# WiFiSensorLTC3566.net
KiCad netlist of a schematic drawn in EAGLE
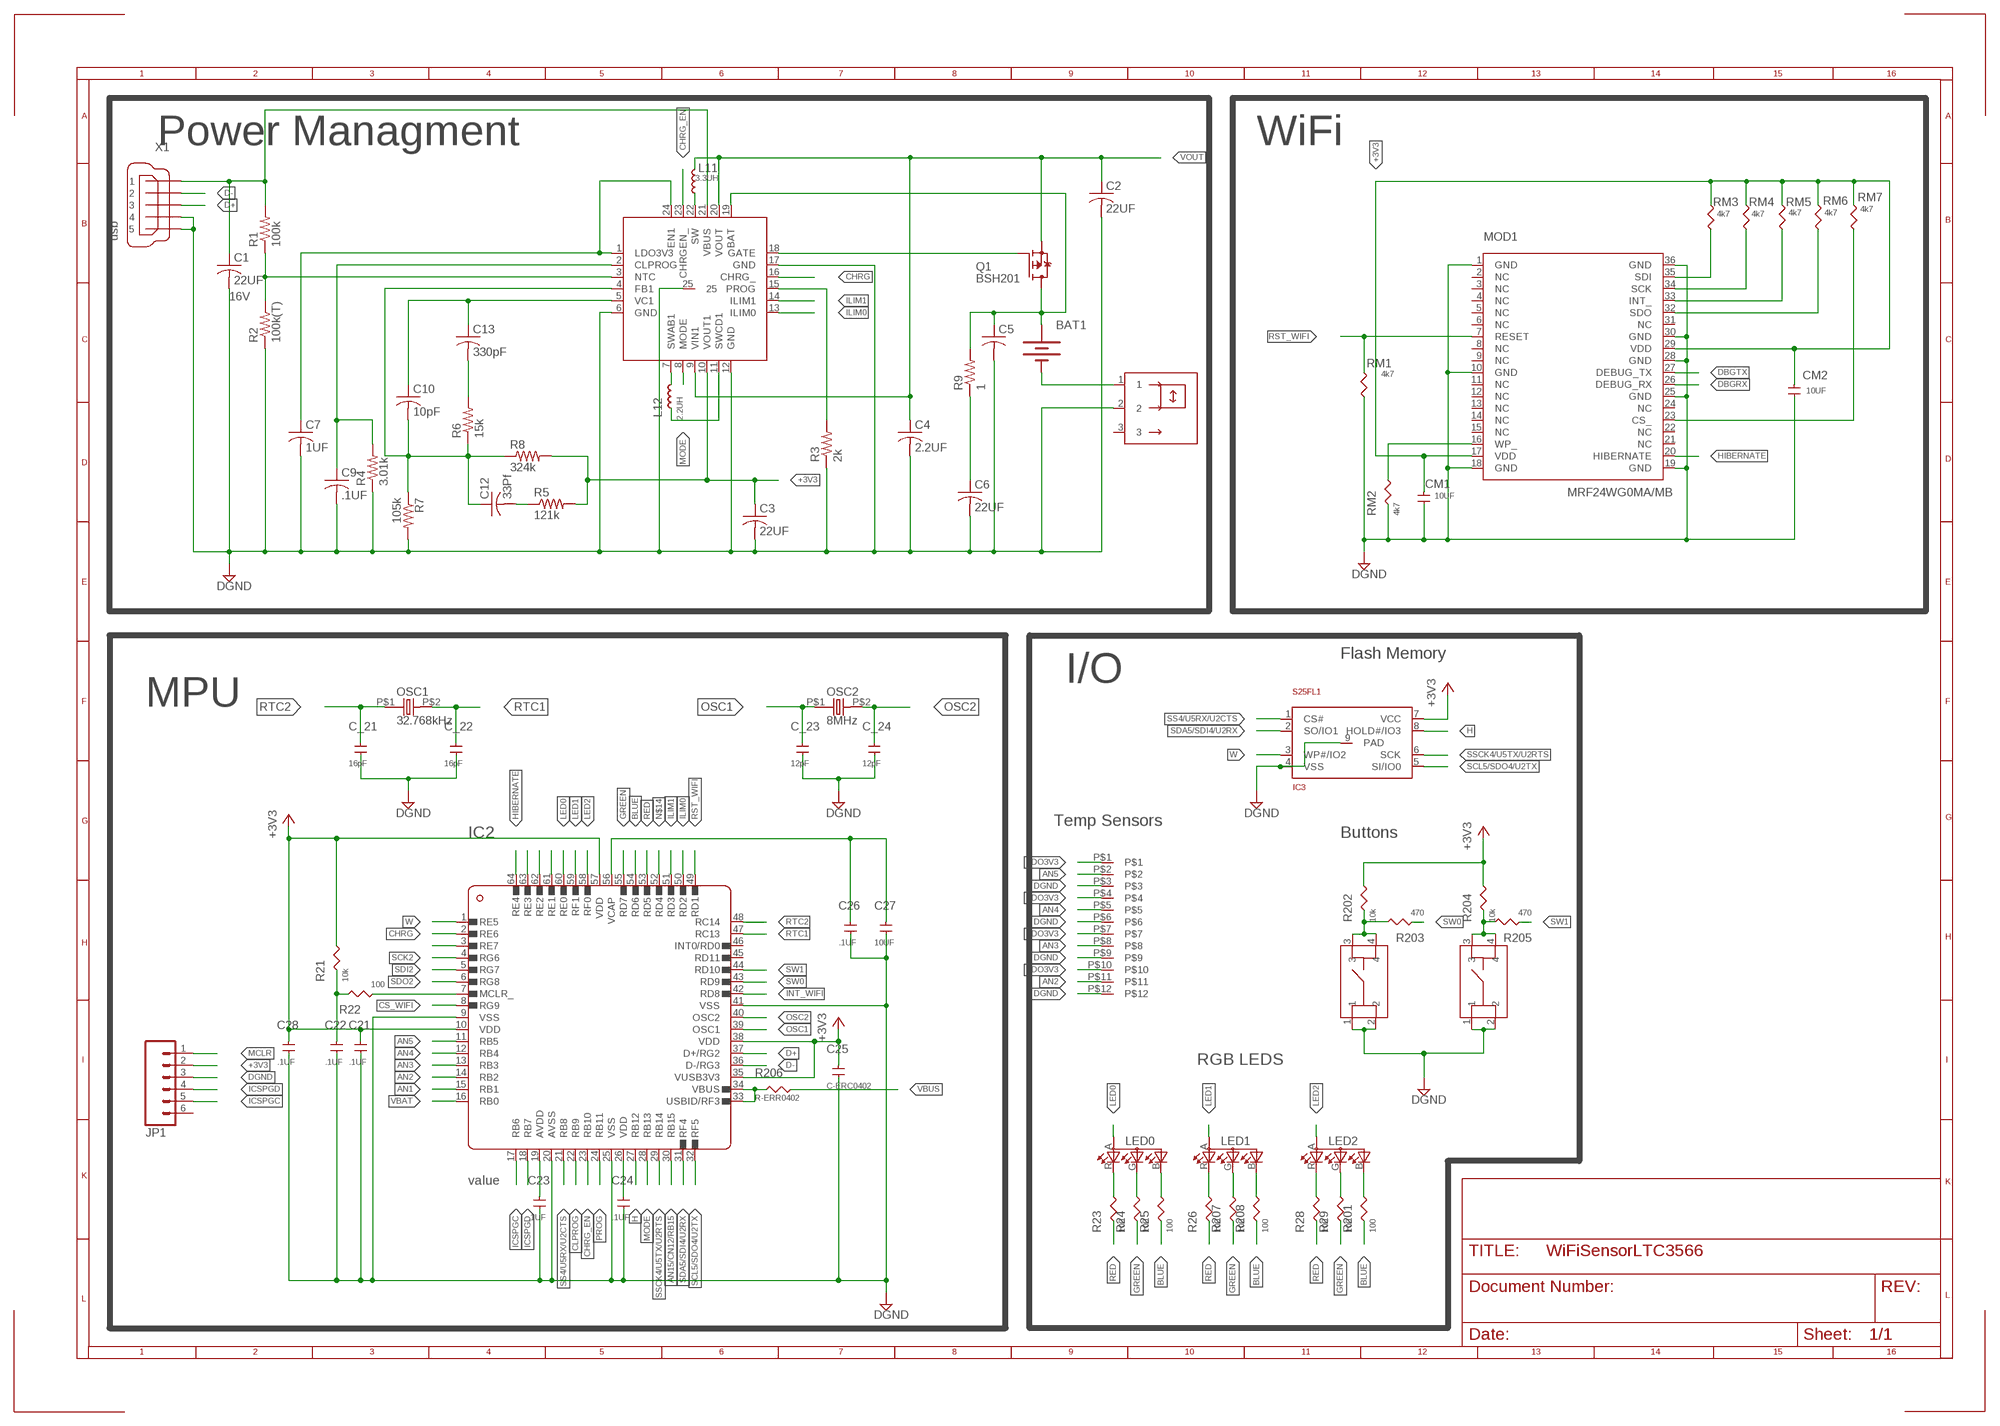
[diagram p0: schematic, sheet 1]

(export (version "E")
  (design (tool "Eeschema 10.0.6"))
  (components
    (comp (ref "BAT1")
      (value "BATTERY245PTH")
      (footprint "eagle-import:BATTCON_245MM_PTH")
      (libsource (lib "eagle-import") (part "BATTERY245PTH"))
    )
    (comp (ref "C1")
      (value "22UF")
      (footprint "eagle-import:C0805")
      (fields (field (name "VOLTAGECOEFFECIENT") "16V"))
      (libsource (lib "eagle-import") (part "C-USC0805"))
    )
    (comp (ref "C2")
      (value "22UF")
      (footprint "eagle-import:C0805")
      (libsource (lib "eagle-import") (part "C-USC0805"))
    )
    (comp (ref "C3")
      (value "22UF")
      (footprint "eagle-import:C0805")
      (libsource (lib "eagle-import") (part "C-USC0805"))
    )
    (comp (ref "C4")
      (value "2.2UF")
      (footprint "eagle-import:C0805")
      (libsource (lib "eagle-import") (part "C-USC0805"))
    )
    (comp (ref "C5")
      (value "C-USC0402")
      (footprint "eagle-import:C0402")
      (libsource (lib "eagle-import") (part "C-USC0402"))
    )
    (comp (ref "C6")
      (value "22UF")
      (footprint "eagle-import:C0805")
      (libsource (lib "eagle-import") (part "C-USC0805"))
    )
    (comp (ref "C7")
      (value "1UF")
      (footprint "eagle-import:C0805")
      (libsource (lib "eagle-import") (part "C-USC0805"))
    )
    (comp (ref "C9")
      (value ".1UF")
      (footprint "eagle-import:C0402")
      (libsource (lib "eagle-import") (part "C-USC0402"))
    )
    (comp (ref "C10")
      (value "10pF")
      (footprint "eagle-import:C0402")
      (libsource (lib "eagle-import") (part "C-USC0402"))
    )
    (comp (ref "C12")
      (value "33Pf")
      (footprint "eagle-import:C0402")
      (libsource (lib "eagle-import") (part "C-USC0402"))
    )
    (comp (ref "C13")
      (value "330pF")
      (footprint "eagle-import:C0402")
      (libsource (lib "eagle-import") (part "C-USC0402"))
    )
    (comp (ref "C21")
      (value ".1UF")
      (footprint "eagle-import:C0402")
      (libsource (lib "eagle-import") (part "C-ERC0402"))
    )
    (comp (ref "C22")
      (value ".1UF")
      (footprint "eagle-import:C0402")
      (libsource (lib "eagle-import") (part "C-ERC0402"))
    )
    (comp (ref "C23")
      (value ".1UF")
      (footprint "eagle-import:C0402")
      (libsource (lib "eagle-import") (part "C-ERC0402"))
    )
    (comp (ref "C24")
      (value ".1UF")
      (footprint "eagle-import:C0402")
      (libsource (lib "eagle-import") (part "C-ERC0402"))
    )
    (comp (ref "C25")
      (value "C-ERC0402")
      (footprint "eagle-import:C0402")
      (libsource (lib "eagle-import") (part "C-ERC0402"))
    )
    (comp (ref "C26")
      (value ".1UF")
      (footprint "eagle-import:C0402")
      (libsource (lib "eagle-import") (part "C-ERC0402"))
    )
    (comp (ref "C27")
      (value "10UF")
      (footprint "eagle-import:C0805")
      (libsource (lib "eagle-import") (part "C-ER"))
    )
    (comp (ref "C28")
      (value ".1UF")
      (footprint "eagle-import:C0402")
      (libsource (lib "eagle-import") (part "C-ERC0402"))
    )
    (comp (ref "CM1")
      (value "10UF")
      (footprint "eagle-import:C0805")
      (libsource (lib "eagle-import") (part "C-ER"))
    )
    (comp (ref "CM2")
      (value "10UF")
      (footprint "eagle-import:C0805")
      (libsource (lib "eagle-import") (part "C-ER"))
    )
    (comp (ref "C_21")
      (value "16pF")
      (footprint "eagle-import:C0402")
      (libsource (lib "eagle-import") (part "C-ERC0402"))
    )
    (comp (ref "C_22")
      (value "16pF")
      (footprint "eagle-import:C0402")
      (libsource (lib "eagle-import") (part "C-ERC0402"))
    )
    (comp (ref "C_23")
      (value "12pF")
      (footprint "eagle-import:C0402")
      (libsource (lib "eagle-import") (part "C-ERC0402"))
    )
    (comp (ref "C_24")
      (value "12pF")
      (footprint "eagle-import:C0402")
      (libsource (lib "eagle-import") (part "C-ERC0402"))
    )
    (comp (ref "IC1")
      (value "LTC3566-2")
      (footprint "eagle-import:QFN24-4X4")
      (libsource (lib "eagle-import") (part "LTC3566"))
    )
    (comp (ref "IC2")
      (value "PICMX32695F512H")
      (footprint "eagle-import:TQFP64")
      (libsource (lib "eagle-import") (part "PICMX32695F512H"))
    )
    (comp (ref "IC3")
      (value "S25FL1")
      (footprint "eagle-import:8WSON")
      (libsource (lib "eagle-import") (part "S25FL1"))
    )
    (comp (ref "JP1")
      (value "M06LOCK")
      (footprint "eagle-import:1X06_LOCK")
      (libsource (lib "eagle-import") (part "M06LOCK"))
    )
    (comp (ref "JP2")
      (value "12_127")
      (footprint "eagle-import:12-127")
      (libsource (lib "eagle-import") (part "12_127"))
    )
    (comp (ref "L11")
      (value "3.3UH")
      (footprint "eagle-import:VLCF5020")
      (libsource (lib "eagle-import") (part "L-ERVLCF5020"))
    )
    (comp (ref "L12")
      (value "2.2UH")
      (footprint "eagle-import:VLCF5020")
      (libsource (lib "eagle-import") (part "L-ERVLCF5020"))
    )
    (comp (ref "LED0")
      (value "1X1RGB")
      (footprint "eagle-import:1X1")
      (libsource (lib "eagle-import") (part "1X1RGB"))
    )
    (comp (ref "LED1")
      (value "1X1RGB")
      (footprint "eagle-import:1X1")
      (libsource (lib "eagle-import") (part "1X1RGB"))
    )
    (comp (ref "LED2")
      (value "1X1RGB")
      (footprint "eagle-import:1X1")
      (libsource (lib "eagle-import") (part "1X1RGB"))
    )
    (comp (ref "MOD1")
      (value "MRF24WG0MA/MB")
      (footprint "eagle-import:MRF24")
      (libsource (lib "eagle-import") (part "MRF24WG0MA/MB"))
    )
    (comp (ref "OSC1")
      (value "32.768kHz")
      (footprint "eagle-import:ECX39")
      (fields (field (name "DIGIPART") "XC1658CT-ND"))
      (libsource (lib "eagle-import") (part "ECX32"))
    )
    (comp (ref "OSC2")
      (value "8MHz")
      (footprint "eagle-import:CX532")
      (fields (field (name "DIGIPART") "XC1658CT-ND"))
      (libsource (lib "eagle-import") (part "CX532"))
    )
    (comp (ref "Q1")
      (value "BSH201")
      (footprint "eagle-import:SOT23")
      (libsource (lib "eagle-import") (part "BSH201"))
    )
    (comp (ref "R1")
      (value "100k")
      (footprint "eagle-import:R0402")
      (libsource (lib "eagle-import") (part "R-US_R0402"))
    )
    (comp (ref "R2")
      (value "100k(T)")
      (footprint "eagle-import:R0402")
      (libsource (lib "eagle-import") (part "R-US_R0402"))
    )
    (comp (ref "R3")
      (value "2k")
      (footprint "eagle-import:R0402")
      (libsource (lib "eagle-import") (part "R-US_R0402"))
    )
    (comp (ref "R4")
      (value "3.01k")
      (footprint "eagle-import:R0402")
      (libsource (lib "eagle-import") (part "R-US_R0402"))
    )
    (comp (ref "R5")
      (value "121k")
      (footprint "eagle-import:R0402")
      (libsource (lib "eagle-import") (part "R-US_R0402"))
    )
    (comp (ref "R6")
      (value "15k")
      (footprint "eagle-import:R0402")
      (libsource (lib "eagle-import") (part "R-US_R0402"))
    )
    (comp (ref "R7")
      (value "105k")
      (footprint "eagle-import:R0402")
      (libsource (lib "eagle-import") (part "R-US_R0402"))
    )
    (comp (ref "R8")
      (value "324k")
      (footprint "eagle-import:R0402")
      (libsource (lib "eagle-import") (part "R-US_R0402"))
    )
    (comp (ref "R9")
      (value "1")
      (footprint "eagle-import:R0402")
      (libsource (lib "eagle-import") (part "R-US_R0402"))
    )
    (comp (ref "R21")
      (value "10k")
      (footprint "eagle-import:R0402")
      (libsource (lib "eagle-import") (part "R-ERR0402"))
    )
    (comp (ref "R22")
      (value "100")
      (footprint "eagle-import:R0402")
      (libsource (lib "eagle-import") (part "R-ERR0402"))
    )
    (comp (ref "R23")
      (value "100")
      (footprint "eagle-import:R0402")
      (libsource (lib "eagle-import") (part "R-ERR0402"))
    )
    (comp (ref "R24")
      (value "100")
      (footprint "eagle-import:R0402")
      (libsource (lib "eagle-import") (part "R-ERR0402"))
    )
    (comp (ref "R25")
      (value "100")
      (footprint "eagle-import:R0402")
      (libsource (lib "eagle-import") (part "R-ERR0402"))
    )
    (comp (ref "R26")
      (value "100")
      (footprint "eagle-import:R0402")
      (libsource (lib "eagle-import") (part "R-ERR0402"))
    )
    (comp (ref "R28")
      (value "100")
      (footprint "eagle-import:R0402")
      (libsource (lib "eagle-import") (part "R-ERR0402"))
    )
    (comp (ref "R29")
      (value "100")
      (footprint "eagle-import:R0402")
      (libsource (lib "eagle-import") (part "R-ERR0402"))
    )
    (comp (ref "R201")
      (value "100")
      (footprint "eagle-import:R0402")
      (libsource (lib "eagle-import") (part "R-ERR0402"))
    )
    (comp (ref "R202")
      (value "10k")
      (footprint "eagle-import:R0402")
      (libsource (lib "eagle-import") (part "R-ERR0402"))
    )
    (comp (ref "R203")
      (value "470")
      (footprint "eagle-import:R0402")
      (libsource (lib "eagle-import") (part "R-ERR0402"))
    )
    (comp (ref "R204")
      (value "10k")
      (footprint "eagle-import:R0402")
      (libsource (lib "eagle-import") (part "R-ERR0402"))
    )
    (comp (ref "R205")
      (value "470")
      (footprint "eagle-import:R0402")
      (libsource (lib "eagle-import") (part "R-ERR0402"))
    )
    (comp (ref "R206")
      (value "R-ERR0402")
      (footprint "eagle-import:R0402")
      (libsource (lib "eagle-import") (part "R-ERR0402"))
    )
    (comp (ref "R207")
      (value "100")
      (footprint "eagle-import:R0402")
      (libsource (lib "eagle-import") (part "R-ERR0402"))
    )
    (comp (ref "R208")
      (value "100")
      (footprint "eagle-import:R0402")
      (libsource (lib "eagle-import") (part "R-ERR0402"))
    )
    (comp (ref "RM1")
      (value "4k7")
      (footprint "eagle-import:R0402")
      (libsource (lib "eagle-import") (part "R-ERR0402"))
    )
    (comp (ref "RM2")
      (value "4k7")
      (footprint "eagle-import:R0402")
      (libsource (lib "eagle-import") (part "R-ERR0402"))
    )
    (comp (ref "RM3")
      (value "4k7")
      (footprint "eagle-import:R0402")
      (libsource (lib "eagle-import") (part "R-ERR0402"))
    )
    (comp (ref "RM4")
      (value "4k7")
      (footprint "eagle-import:R0402")
      (libsource (lib "eagle-import") (part "R-ERR0402"))
    )
    (comp (ref "RM5")
      (value "4k7")
      (footprint "eagle-import:R0402")
      (libsource (lib "eagle-import") (part "R-ERR0402"))
    )
    (comp (ref "RM6")
      (value "4k7")
      (footprint "eagle-import:R0402")
      (libsource (lib "eagle-import") (part "R-ERR0402"))
    )
    (comp (ref "RM7")
      (value "4k7")
      (footprint "eagle-import:R0402")
      (libsource (lib "eagle-import") (part "R-ERR0402"))
    )
    (comp (ref "SW0")
      (value "ADTS")
      (footprint "eagle-import:4X5")
      (libsource (lib "eagle-import") (part "ADTS"))
    )
    (comp (ref "SW1")
      (value "ADTS")
      (footprint "eagle-import:4X5")
      (libsource (lib "eagle-import") (part "ADTS"))
    )
    (comp (ref "SW2")
      (value "C&K_JS")
      (footprint "eagle-import:SAQN")
      (libsource (lib "eagle-import") (part "C&K_JS"))
    )
    (comp (ref "X1")
      (value "usb")
      (footprint "eagle-import:UX60A-MB-5ST")
      (libsource (lib "eagle-import") (part "MINI-USB-UX60A-MB-5ST"))
    )
  )
  (nets
    (net (code "1") (name "+3V3") (class "Default")
      (node (ref "C21") (pin "2") (pinfunction "P$2_2") (pintype "bidirectional"))
      (node (ref "C24") (pin "2") (pinfunction "P$2_2") (pintype "bidirectional"))
      (node (ref "C25") (pin "2") (pinfunction "P$2_2") (pintype "bidirectional"))
      (node (ref "C28") (pin "2") (pinfunction "P$2_2") (pintype "bidirectional"))
      (node (ref "C3") (pin "1") (pinfunction "1_1") (pintype "passive"))
      (node (ref "CM1") (pin "2") (pinfunction "P$2_2") (pintype "bidirectional"))
      (node (ref "CM2") (pin "2") (pinfunction "P$2_2") (pintype "bidirectional"))
      (node (ref "IC1") (pin "10") (pinfunction "VOUT1_10") (pintype "bidirectional"))
      (node (ref "IC2") (pin "10") (pinfunction "VDD_10") (pintype "bidirectional"))
      (node (ref "IC2") (pin "26") (pinfunction "VDD_26") (pintype "bidirectional"))
      (node (ref "IC2") (pin "35") (pinfunction "VUSB3V3_35") (pintype "bidirectional"))
      (node (ref "IC2") (pin "38") (pinfunction "VDD_38") (pintype "bidirectional"))
      (node (ref "IC2") (pin "57") (pinfunction "VDD_57") (pintype "bidirectional"))
      (node (ref "IC3") (pin "7") (pinfunction "VCC_7") (pintype "bidirectional"))
      (node (ref "JP1") (pin "2") (pinfunction "2_2") (pintype "passive"))
      (node (ref "MOD1") (pin "17") (pinfunction "VDD_17") (pintype "bidirectional"))
      (node (ref "MOD1") (pin "29") (pinfunction "VDD_29") (pintype "bidirectional"))
      (node (ref "R202") (pin "2") (pinfunction "P$2_2") (pintype "bidirectional"))
      (node (ref "R204") (pin "2") (pinfunction "P$2_2") (pintype "bidirectional"))
      (node (ref "R21") (pin "2") (pinfunction "P$2_2") (pintype "bidirectional"))
      (node (ref "R5") (pin "2") (pinfunction "2_2") (pintype "passive"))
      (node (ref "R8") (pin "2") (pinfunction "2_2") (pintype "passive"))
      (node (ref "RM3") (pin "2") (pinfunction "P$2_2") (pintype "bidirectional"))
      (node (ref "RM4") (pin "2") (pinfunction "P$2_2") (pintype "bidirectional"))
      (node (ref "RM5") (pin "2") (pinfunction "P$2_2") (pintype "bidirectional"))
      (node (ref "RM6") (pin "2") (pinfunction "P$2_2") (pintype "bidirectional"))
      (node (ref "RM7") (pin "2") (pinfunction "P$2_2") (pintype "bidirectional"))
    )
    (net (code "2") (name "AN1") (class "Default")
      (node (ref "IC2") (pin "15") (pinfunction "RB1_15") (pintype "bidirectional"))
    )
    (net (code "3") (name "AN2") (class "Default")
      (node (ref "IC2") (pin "14") (pinfunction "RB2_14") (pintype "bidirectional"))
      (node (ref "JP2") (pin "P$11") (pinfunction "P$11_P$11") (pintype "bidirectional"))
    )
    (net (code "4") (name "AN3") (class "Default")
      (node (ref "IC2") (pin "13") (pinfunction "RB3_13") (pintype "bidirectional"))
      (node (ref "JP2") (pin "P$8") (pinfunction "P$8_P$8") (pintype "bidirectional"))
    )
    (net (code "5") (name "AN4") (class "Default")
      (node (ref "IC2") (pin "12") (pinfunction "RB4_12") (pintype "bidirectional"))
      (node (ref "JP2") (pin "P$5") (pinfunction "P$5_P$5") (pintype "bidirectional"))
    )
    (net (code "6") (name "AN5") (class "Default")
      (node (ref "IC2") (pin "11") (pinfunction "RB5_11") (pintype "bidirectional"))
      (node (ref "JP2") (pin "P$2") (pinfunction "P$2_P$2") (pintype "bidirectional"))
    )
    (net (code "7") (name "AN15{slash}CN12{slash}RB15") (class "Default")
      (node (ref "IC2") (pin "30") (pinfunction "RB15_30") (pintype "bidirectional"))
    )
    (net (code "8") (name "BLUE") (class "Default")
      (node (ref "IC2") (pin "54") (pinfunction "RD6_54") (pintype "bidirectional"))
      (node (ref "R201") (pin "1") (pinfunction "P$1_1") (pintype "bidirectional"))
      (node (ref "R208") (pin "1") (pinfunction "P$1_1") (pintype "bidirectional"))
      (node (ref "R25") (pin "1") (pinfunction "P$1_1") (pintype "bidirectional"))
    )
    (net (code "9") (name "CHRG") (class "Default")
      (node (ref "IC1") (pin "16") (pinfunction "CHRG__16") (pintype "bidirectional"))
      (node (ref "IC2") (pin "2") (pinfunction "RE6_2") (pintype "bidirectional"))
    )
    (net (code "10") (name "CHRG_EN") (class "Default")
      (node (ref "IC1") (pin "23") (pinfunction "CHRGEN__23") (pintype "bidirectional"))
      (node (ref "IC2") (pin "23") (pinfunction "RB10_23") (pintype "bidirectional"))
    )
    (net (code "11") (name "CLPROG") (class "Default")
      (node (ref "C9") (pin "1") (pinfunction "1_1") (pintype "passive"))
      (node (ref "IC1") (pin "2") (pinfunction "CLPROG_2") (pintype "bidirectional"))
      (node (ref "IC2") (pin "22") (pinfunction "RB9_22") (pintype "bidirectional"))
      (node (ref "R4") (pin "2") (pinfunction "2_2") (pintype "passive"))
    )
    (net (code "12") (name "CS_WIFI") (class "Default")
      (node (ref "IC2") (pin "8") (pinfunction "RG9_8") (pintype "bidirectional"))
      (node (ref "MOD1") (pin "23") (pinfunction "CS__23") (pintype "bidirectional"))
      (node (ref "RM7") (pin "1") (pinfunction "P$1_1") (pintype "bidirectional"))
    )
    (net (code "13") (name "D+") (class "Default")
      (node (ref "IC2") (pin "37") (pinfunction "D+/RG2_37") (pintype "bidirectional"))
      (node (ref "X1") (pin "3") (pinfunction "3_3") (pintype "input"))
    )
    (net (code "14") (name "D-") (class "Default")
      (node (ref "IC2") (pin "36") (pinfunction "D-/RG3_36") (pintype "bidirectional"))
      (node (ref "X1") (pin "2") (pinfunction "2_2") (pintype "input"))
    )
    (net (code "15") (name "DBGRX") (class "Default")
      (node (ref "MOD1") (pin "26") (pinfunction "DEBUG_RX_26") (pintype "bidirectional"))
    )
    (net (code "16") (name "DBGTX") (class "Default")
      (node (ref "MOD1") (pin "27") (pinfunction "DEBUG_TX_27") (pintype "bidirectional"))
    )
    (net (code "17") (name "DGND") (class "Default")
      (node (ref "C1") (pin "2") (pinfunction "2_2") (pintype "passive"))
      (node (ref "C2") (pin "2") (pinfunction "2_2") (pintype "passive"))
      (node (ref "C21") (pin "1") (pinfunction "P$1_1") (pintype "bidirectional"))
      (node (ref "C22") (pin "1") (pinfunction "P$1_1") (pintype "bidirectional"))
      (node (ref "C23") (pin "1") (pinfunction "P$1_1") (pintype "bidirectional"))
      (node (ref "C24") (pin "1") (pinfunction "P$1_1") (pintype "bidirectional"))
      (node (ref "C25") (pin "1") (pinfunction "P$1_1") (pintype "bidirectional"))
      (node (ref "C26") (pin "1") (pinfunction "P$1_1") (pintype "bidirectional"))
      (node (ref "C27") (pin "1") (pinfunction "P$1_1") (pintype "bidirectional"))
      (node (ref "C28") (pin "1") (pinfunction "P$1_1") (pintype "bidirectional"))
      (node (ref "C3") (pin "2") (pinfunction "2_2") (pintype "passive"))
      (node (ref "C4") (pin "2") (pinfunction "2_2") (pintype "passive"))
      (node (ref "C5") (pin "2") (pinfunction "2_2") (pintype "passive"))
      (node (ref "C6") (pin "2") (pinfunction "2_2") (pintype "passive"))
      (node (ref "C7") (pin "2") (pinfunction "2_2") (pintype "passive"))
      (node (ref "C9") (pin "2") (pinfunction "2_2") (pintype "passive"))
      (node (ref "CM1") (pin "1") (pinfunction "P$1_1") (pintype "bidirectional"))
      (node (ref "CM2") (pin "1") (pinfunction "P$1_1") (pintype "bidirectional"))
      (node (ref "C_21") (pin "1") (pinfunction "P$1_1") (pintype "bidirectional"))
      (node (ref "C_22") (pin "1") (pinfunction "P$1_1") (pintype "bidirectional"))
      (node (ref "C_23") (pin "1") (pinfunction "P$1_1") (pintype "bidirectional"))
      (node (ref "C_24") (pin "1") (pinfunction "P$1_1") (pintype "bidirectional"))
      (node (ref "IC1") (pin "12") (pinfunction "GND_12") (pintype "bidirectional"))
      (node (ref "IC1") (pin "17") (pinfunction "GND_17") (pintype "bidirectional"))
      (node (ref "IC1") (pin "25") (pinfunction "25_25") (pintype "bidirectional"))
      (node (ref "IC1") (pin "6") (pinfunction "GND_6") (pintype "bidirectional"))
      (node (ref "IC2") (pin "20") (pinfunction "AVSS_20") (pintype "bidirectional"))
      (node (ref "IC2") (pin "25") (pinfunction "VSS_25") (pintype "bidirectional"))
      (node (ref "IC2") (pin "41") (pinfunction "VSS_41") (pintype "bidirectional"))
      (node (ref "IC2") (pin "9") (pinfunction "VSS_9") (pintype "bidirectional"))
      (node (ref "IC3") (pin "4") (pinfunction "VSS_4") (pintype "bidirectional"))
      (node (ref "IC3") (pin "9") (pinfunction "PAD_9") (pintype "bidirectional"))
      (node (ref "JP1") (pin "3") (pinfunction "3_3") (pintype "passive"))
      (node (ref "JP2") (pin "P$12") (pinfunction "P$12_P$12") (pintype "bidirectional"))
      (node (ref "JP2") (pin "P$3") (pinfunction "P$3_P$3") (pintype "bidirectional"))
      (node (ref "JP2") (pin "P$6") (pinfunction "P$6_P$6") (pintype "bidirectional"))
      (node (ref "JP2") (pin "P$9") (pinfunction "P$9_P$9") (pintype "bidirectional"))
      (node (ref "MOD1") (pin "1") (pinfunction "GND_1") (pintype "bidirectional"))
      (node (ref "MOD1") (pin "10") (pinfunction "GND_10") (pintype "bidirectional"))
      (node (ref "MOD1") (pin "18") (pinfunction "GND_18") (pintype "bidirectional"))
      (node (ref "MOD1") (pin "19") (pinfunction "GND_19") (pintype "bidirectional"))
      (node (ref "MOD1") (pin "25") (pinfunction "GND_25") (pintype "bidirectional"))
      (node (ref "MOD1") (pin "28") (pinfunction "GND_28") (pintype "bidirectional"))
      (node (ref "MOD1") (pin "30") (pinfunction "GND_30") (pintype "bidirectional"))
      (node (ref "MOD1") (pin "36") (pinfunction "GND_36") (pintype "bidirectional"))
      (node (ref "R2") (pin "1") (pinfunction "1_1") (pintype "passive"))
      (node (ref "R3") (pin "1") (pinfunction "1_1") (pintype "passive"))
      (node (ref "R4") (pin "1") (pinfunction "1_1") (pintype "passive"))
      (node (ref "R7") (pin "2") (pinfunction "2_2") (pintype "passive"))
      (node (ref "RM1") (pin "1") (pinfunction "P$1_1") (pintype "bidirectional"))
      (node (ref "RM2") (pin "1") (pinfunction "P$1_1") (pintype "bidirectional"))
      (node (ref "SW0") (pin "1") (pinfunction "1_1") (pintype "bidirectional"))
      (node (ref "SW0") (pin "2") (pinfunction "2_2") (pintype "bidirectional"))
      (node (ref "SW1") (pin "1") (pinfunction "1_1") (pintype "bidirectional"))
      (node (ref "SW1") (pin "2") (pinfunction "2_2") (pintype "bidirectional"))
      (node (ref "SW2") (pin "2") (pinfunction "2_2") (pintype "bidirectional"))
      (node (ref "X1") (pin "4") (pinfunction "4_4") (pintype "input"))
      (node (ref "X1") (pin "5") (pinfunction "5_5") (pintype "input"))
    )
    (net (code "18") (name "GREEN") (class "Default")
      (node (ref "IC2") (pin "55") (pinfunction "RD7_55") (pintype "bidirectional"))
      (node (ref "R207") (pin "1") (pinfunction "P$1_1") (pintype "bidirectional"))
      (node (ref "R24") (pin "1") (pinfunction "P$1_1") (pintype "bidirectional"))
      (node (ref "R29") (pin "1") (pinfunction "P$1_1") (pintype "bidirectional"))
    )
    (net (code "19") (name "H") (class "Default")
      (node (ref "IC2") (pin "27") (pinfunction "RB12_27") (pintype "bidirectional"))
      (node (ref "IC3") (pin "8") (pinfunction "HOLD#/IO3_8") (pintype "bidirectional"))
    )
    (net (code "20") (name "HIBERNATE") (class "Default")
      (node (ref "IC2") (pin "64") (pinfunction "RE4_64") (pintype "bidirectional"))
      (node (ref "MOD1") (pin "20") (pinfunction "HIBERNATE_20") (pintype "bidirectional"))
    )
    (net (code "21") (name "ICSPGC") (class "Default")
      (node (ref "IC2") (pin "17") (pinfunction "RB6_17") (pintype "bidirectional"))
      (node (ref "JP1") (pin "5") (pinfunction "5_5") (pintype "passive"))
    )
    (net (code "22") (name "ICSPGD") (class "Default")
      (node (ref "IC2") (pin "18") (pinfunction "RB7_18") (pintype "bidirectional"))
      (node (ref "JP1") (pin "4") (pinfunction "4_4") (pintype "passive"))
    )
    (net (code "23") (name "ILIM0") (class "Default")
      (node (ref "IC1") (pin "13") (pinfunction "ILIM0_13") (pintype "bidirectional"))
      (node (ref "IC2") (pin "50") (pinfunction "RD2_50") (pintype "bidirectional"))
    )
    (net (code "24") (name "ILIM1") (class "Default")
      (node (ref "IC1") (pin "14") (pinfunction "ILIM1_14") (pintype "bidirectional"))
      (node (ref "IC2") (pin "51") (pinfunction "RD3_51") (pintype "bidirectional"))
    )
    (net (code "25") (name "INT_WIFI") (class "Default")
      (node (ref "IC2") (pin "42") (pinfunction "RD8_42") (pintype "bidirectional"))
      (node (ref "MOD1") (pin "33") (pinfunction "INT__33") (pintype "bidirectional"))
      (node (ref "RM5") (pin "1") (pinfunction "P$1_1") (pintype "bidirectional"))
    )
    (net (code "26") (name "LDO3V3") (class "Default")
      (node (ref "C23") (pin "2") (pinfunction "P$2_2") (pintype "bidirectional"))
      (node (ref "C7") (pin "1") (pinfunction "1_1") (pintype "passive"))
      (node (ref "IC1") (pin "1") (pinfunction "LDO3V3_1") (pintype "bidirectional"))
      (node (ref "IC1") (pin "24") (pinfunction "EN1_24") (pintype "bidirectional"))
      (node (ref "IC2") (pin "19") (pinfunction "AVDD_19") (pintype "bidirectional"))
      (node (ref "JP2") (pin "P$1") (pinfunction "P$1_P$1") (pintype "bidirectional"))
      (node (ref "JP2") (pin "P$10") (pinfunction "P$10_P$10") (pintype "bidirectional"))
      (node (ref "JP2") (pin "P$4") (pinfunction "P$4_P$4") (pintype "bidirectional"))
      (node (ref "JP2") (pin "P$7") (pinfunction "P$7_P$7") (pintype "bidirectional"))
    )
    (net (code "27") (name "LED0") (class "Default")
      (node (ref "IC2") (pin "60") (pinfunction "RE0_60") (pintype "bidirectional"))
      (node (ref "LED0") (pin "A") (pinfunction "A2_A") (pintype "passive"))
    )
    (net (code "28") (name "LED1") (class "Default")
      (node (ref "IC2") (pin "59") (pinfunction "RF1_59") (pintype "bidirectional"))
      (node (ref "LED1") (pin "A") (pinfunction "A2_A") (pintype "passive"))
    )
    (net (code "29") (name "LED2") (class "Default")
      (node (ref "IC2") (pin "58") (pinfunction "RF0_58") (pintype "bidirectional"))
      (node (ref "LED2") (pin "A") (pinfunction "A2_A") (pintype "passive"))
    )
    (net (code "30") (name "MCLR") (class "Default")
      (node (ref "C22") (pin "2") (pinfunction "P$2_2") (pintype "bidirectional"))
      (node (ref "JP1") (pin "1") (pinfunction "1_1") (pintype "passive"))
      (node (ref "R21") (pin "1") (pinfunction "P$1_1") (pintype "bidirectional"))
      (node (ref "R22") (pin "2") (pinfunction "P$2_2") (pintype "bidirectional"))
    )
    (net (code "31") (name "MODE") (class "Default")
      (node (ref "IC1") (pin "8") (pinfunction "MODE_8") (pintype "bidirectional"))
      (node (ref "IC2") (pin "28") (pinfunction "RB13_28") (pintype "bidirectional"))
    )
    (net (code "32") (name "N$14") (class "Default")
      (node (ref "IC2") (pin "52") (pinfunction "RD4_52") (pintype "bidirectional"))
    )
    (net (code "33") (name "Net-(BAT1--)") (class "Default")
      (node (ref "BAT1") (pin "2") (pinfunction "-_2") (pintype "power_in"))
      (node (ref "SW2") (pin "1") (pinfunction "1_1") (pintype "bidirectional"))
    )
    (net (code "34") (name "Net-(C6-Pad1)") (class "Default")
      (node (ref "C6") (pin "1") (pinfunction "1_1") (pintype "passive"))
      (node (ref "R9") (pin "1") (pinfunction "1_1") (pintype "passive"))
    )
    (net (code "35") (name "Net-(C12-Pad2)") (class "Default")
      (node (ref "C12") (pin "2") (pinfunction "2_2") (pintype "passive"))
      (node (ref "R5") (pin "1") (pinfunction "1_1") (pintype "passive"))
    )
    (net (code "36") (name "Net-(C13-Pad2)") (class "Default")
      (node (ref "C13") (pin "2") (pinfunction "2_2") (pintype "passive"))
      (node (ref "R6") (pin "2") (pinfunction "2_2") (pintype "passive"))
    )
    (net (code "37") (name "Net-(C26-P$2)") (class "Default")
      (node (ref "C26") (pin "2") (pinfunction "P$2_2") (pintype "bidirectional"))
      (node (ref "C27") (pin "2") (pinfunction "P$2_2") (pintype "bidirectional"))
      (node (ref "IC2") (pin "56") (pinfunction "VCAP_56") (pintype "bidirectional"))
    )
    (net (code "38") (name "Net-(IC1-FB1)") (class "Default")
      (node (ref "C10") (pin "2") (pinfunction "2_2") (pintype "passive"))
      (node (ref "C12") (pin "1") (pinfunction "1_1") (pintype "passive"))
      (node (ref "IC1") (pin "4") (pinfunction "FB1_4") (pintype "bidirectional"))
      (node (ref "R6") (pin "1") (pinfunction "1_1") (pintype "passive"))
      (node (ref "R7") (pin "1") (pinfunction "1_1") (pintype "passive"))
      (node (ref "R8") (pin "1") (pinfunction "1_1") (pintype "passive"))
    )
    (net (code "39") (name "Net-(IC1-GATE)") (class "Default")
      (node (ref "IC1") (pin "18") (pinfunction "GATE_18") (pintype "bidirectional"))
      (node (ref "Q1") (pin "1") (pinfunction "G_1") (pintype "passive"))
    )
    (net (code "40") (name "Net-(IC1-NTC)") (class "Default")
      (node (ref "IC1") (pin "3") (pinfunction "NTC_3") (pintype "bidirectional"))
      (node (ref "R1") (pin "1") (pinfunction "1_1") (pintype "passive"))
      (node (ref "R2") (pin "2") (pinfunction "2_2") (pintype "passive"))
    )
    (net (code "41") (name "Net-(IC1-SW)") (class "Default")
      (node (ref "IC1") (pin "22") (pinfunction "SW_22") (pintype "bidirectional"))
      (node (ref "L11") (pin "P$1") (pinfunction "P$1_P$1") (pintype "bidirectional"))
    )
    (net (code "42") (name "Net-(IC1-SWAB1)") (class "Default")
      (node (ref "IC1") (pin "7") (pinfunction "SWAB1_7") (pintype "bidirectional"))
      (node (ref "L12") (pin "P$2") (pinfunction "P$2_P$2") (pintype "bidirectional"))
    )
    (net (code "43") (name "Net-(IC1-SWCD1)") (class "Default")
      (node (ref "IC1") (pin "11") (pinfunction "SWCD1_11") (pintype "bidirectional"))
      (node (ref "L12") (pin "P$1") (pinfunction "P$1_P$1") (pintype "bidirectional"))
    )
    (net (code "44") (name "Net-(IC1-VC1)") (class "Default")
      (node (ref "C10") (pin "1") (pinfunction "1_1") (pintype "passive"))
      (node (ref "C13") (pin "1") (pinfunction "1_1") (pintype "passive"))
      (node (ref "IC1") (pin "5") (pinfunction "VC1_5") (pintype "bidirectional"))
    )
    (net (code "45") (name "Net-(IC2-MCLR_)") (class "Default")
      (node (ref "IC2") (pin "7") (pinfunction "MCLR__7") (pintype "bidirectional"))
      (node (ref "R22") (pin "1") (pinfunction "P$1_1") (pintype "bidirectional"))
    )
    (net (code "46") (name "Net-(IC2-USBID{slash}RF3)") (class "Default")
      (node (ref "IC2") (pin "33") (pinfunction "USBID/RF3_33") (pintype "bidirectional"))
      (node (ref "IC2") (pin "34") (pinfunction "VBUS_34") (pintype "bidirectional"))
      (node (ref "R206") (pin "1") (pinfunction "P$1_1") (pintype "bidirectional"))
    )
    (net (code "47") (name "Net-(LED0-CBLUE)") (class "Default")
      (node (ref "LED0") (pin "G") (pinfunction "CBLUE_G") (pintype "passive"))
      (node (ref "R24") (pin "2") (pinfunction "P$2_2") (pintype "bidirectional"))
    )
    (net (code "48") (name "Net-(LED0-CGREEN)") (class "Default")
      (node (ref "LED0") (pin "B") (pinfunction "CGREEN_B") (pintype "passive"))
      (node (ref "R25") (pin "2") (pinfunction "P$2_2") (pintype "bidirectional"))
    )
    (net (code "49") (name "Net-(LED0-CRED)") (class "Default")
      (node (ref "LED0") (pin "R") (pinfunction "CRED_R") (pintype "passive"))
      (node (ref "R23") (pin "2") (pinfunction "P$2_2") (pintype "bidirectional"))
    )
    (net (code "50") (name "Net-(LED1-CBLUE)") (class "Default")
      (node (ref "LED1") (pin "G") (pinfunction "CBLUE_G") (pintype "passive"))
      (node (ref "R207") (pin "2") (pinfunction "P$2_2") (pintype "bidirectional"))
    )
    (net (code "51") (name "Net-(LED1-CGREEN)") (class "Default")
      (node (ref "LED1") (pin "B") (pinfunction "CGREEN_B") (pintype "passive"))
      (node (ref "R208") (pin "2") (pinfunction "P$2_2") (pintype "bidirectional"))
    )
    (net (code "52") (name "Net-(LED1-CRED)") (class "Default")
      (node (ref "LED1") (pin "R") (pinfunction "CRED_R") (pintype "passive"))
      (node (ref "R26") (pin "2") (pinfunction "P$2_2") (pintype "bidirectional"))
    )
    (net (code "53") (name "Net-(LED2-CBLUE)") (class "Default")
      (node (ref "LED2") (pin "G") (pinfunction "CBLUE_G") (pintype "passive"))
      (node (ref "R29") (pin "2") (pinfunction "P$2_2") (pintype "bidirectional"))
    )
    (net (code "54") (name "Net-(LED2-CGREEN)") (class "Default")
      (node (ref "LED2") (pin "B") (pinfunction "CGREEN_B") (pintype "passive"))
      (node (ref "R201") (pin "2") (pinfunction "P$2_2") (pintype "bidirectional"))
    )
    (net (code "55") (name "Net-(LED2-CRED)") (class "Default")
      (node (ref "LED2") (pin "R") (pinfunction "CRED_R") (pintype "passive"))
      (node (ref "R28") (pin "2") (pinfunction "P$2_2") (pintype "bidirectional"))
    )
    (net (code "56") (name "Net-(MOD1-WP_)") (class "Default")
      (node (ref "MOD1") (pin "16") (pinfunction "WP__16") (pintype "bidirectional"))
      (node (ref "RM2") (pin "2") (pinfunction "P$2_2") (pintype "bidirectional"))
    )
    (net (code "57") (name "Net-(R202-P$1)") (class "Default")
      (node (ref "R202") (pin "1") (pinfunction "P$1_1") (pintype "bidirectional"))
      (node (ref "R203") (pin "2") (pinfunction "P$2_2") (pintype "bidirectional"))
      (node (ref "SW0") (pin "3") (pinfunction "3_3") (pintype "bidirectional"))
      (node (ref "SW0") (pin "4") (pinfunction "4_4") (pintype "bidirectional"))
    )
    (net (code "58") (name "Net-(R204-P$1)") (class "Default")
      (node (ref "R204") (pin "1") (pinfunction "P$1_1") (pintype "bidirectional"))
      (node (ref "R205") (pin "2") (pinfunction "P$2_2") (pintype "bidirectional"))
      (node (ref "SW1") (pin "3") (pinfunction "3_3") (pintype "bidirectional"))
      (node (ref "SW1") (pin "4") (pinfunction "4_4") (pintype "bidirectional"))
    )
    (net (code "59") (name "OSC1") (class "Default")
      (node (ref "C_23") (pin "2") (pinfunction "P$2_2") (pintype "bidirectional"))
      (node (ref "IC2") (pin "39") (pinfunction "OSC1_39") (pintype "bidirectional"))
      (node (ref "OSC2") (pin "P$1") (pinfunction "1_P$1") (pintype "passive"))
    )
    (net (code "60") (name "OSC2") (class "Default")
      (node (ref "C_24") (pin "2") (pinfunction "P$2_2") (pintype "bidirectional"))
      (node (ref "IC2") (pin "40") (pinfunction "OSC2_40") (pintype "bidirectional"))
      (node (ref "OSC2") (pin "P$2") (pinfunction "2_P$2") (pintype "passive"))
    )
    (net (code "61") (name "PROG") (class "Default")
      (node (ref "IC1") (pin "15") (pinfunction "PROG_15") (pintype "bidirectional"))
      (node (ref "IC2") (pin "24") (pinfunction "RB11_24") (pintype "bidirectional"))
      (node (ref "R3") (pin "2") (pinfunction "2_2") (pintype "passive"))
    )
    (net (code "62") (name "RED") (class "Default")
      (node (ref "IC2") (pin "53") (pinfunction "RD5_53") (pintype "bidirectional"))
      (node (ref "R23") (pin "1") (pinfunction "P$1_1") (pintype "bidirectional"))
      (node (ref "R26") (pin "1") (pinfunction "P$1_1") (pintype "bidirectional"))
      (node (ref "R28") (pin "1") (pinfunction "P$1_1") (pintype "bidirectional"))
    )
    (net (code "63") (name "RST_WIFI") (class "Default")
      (node (ref "IC2") (pin "49") (pinfunction "RD1_49") (pintype "bidirectional"))
      (node (ref "MOD1") (pin "7") (pinfunction "RESET_7") (pintype "bidirectional"))
      (node (ref "RM1") (pin "2") (pinfunction "P$2_2") (pintype "bidirectional"))
    )
    (net (code "64") (name "RTC1") (class "Default")
      (node (ref "C_22") (pin "2") (pinfunction "P$2_2") (pintype "bidirectional"))
      (node (ref "IC2") (pin "47") (pinfunction "RC13_47") (pintype "bidirectional"))
      (node (ref "OSC1") (pin "P$2") (pinfunction "2_P$2") (pintype "passive"))
    )
    (net (code "65") (name "RTC2") (class "Default")
      (node (ref "C_21") (pin "2") (pinfunction "P$2_2") (pintype "bidirectional"))
      (node (ref "IC2") (pin "48") (pinfunction "RC14_48") (pintype "bidirectional"))
      (node (ref "OSC1") (pin "P$1") (pinfunction "1_P$1") (pintype "passive"))
    )
    (net (code "66") (name "SCK2") (class "Default")
      (node (ref "IC2") (pin "4") (pinfunction "RG6_4") (pintype "bidirectional"))
      (node (ref "MOD1") (pin "34") (pinfunction "SCK_34") (pintype "bidirectional"))
      (node (ref "RM4") (pin "1") (pinfunction "P$1_1") (pintype "bidirectional"))
    )
    (net (code "67") (name "SCL5{slash}SDO4{slash}U2TX") (class "Default")
      (node (ref "IC2") (pin "32") (pinfunction "RF5_32") (pintype "bidirectional"))
      (node (ref "IC3") (pin "5") (pinfunction "SI/IO0_5") (pintype "bidirectional"))
    )
    (net (code "68") (name "SDA5{slash}SDI4{slash}U2RX") (class "Default")
      (node (ref "IC2") (pin "31") (pinfunction "RF4_31") (pintype "bidirectional"))
      (node (ref "IC3") (pin "2") (pinfunction "SO/IO1_2") (pintype "bidirectional"))
    )
    (net (code "69") (name "SDI2") (class "Default")
      (node (ref "IC2") (pin "5") (pinfunction "RG7_5") (pintype "bidirectional"))
      (node (ref "MOD1") (pin "32") (pinfunction "SDO_32") (pintype "bidirectional"))
      (node (ref "RM6") (pin "1") (pinfunction "P$1_1") (pintype "bidirectional"))
    )
    (net (code "70") (name "SDO2") (class "Default")
      (node (ref "IC2") (pin "6") (pinfunction "RG8_6") (pintype "bidirectional"))
      (node (ref "MOD1") (pin "35") (pinfunction "SDI_35") (pintype "bidirectional"))
      (node (ref "RM3") (pin "1") (pinfunction "P$1_1") (pintype "bidirectional"))
    )
    (net (code "71") (name "SS4{slash}U5RX{slash}U2CTS") (class "Default")
      (node (ref "IC2") (pin "21") (pinfunction "RB8_21") (pintype "bidirectional"))
      (node (ref "IC3") (pin "1") (pinfunction "CS#_1") (pintype "bidirectional"))
    )
    (net (code "72") (name "SSCK4{slash}U5TX{slash}U2RTS") (class "Default")
      (node (ref "IC2") (pin "29") (pinfunction "RB14_29") (pintype "bidirectional"))
      (node (ref "IC3") (pin "6") (pinfunction "SCK_6") (pintype "bidirectional"))
    )
    (net (code "73") (name "SW0") (class "Default")
      (node (ref "IC2") (pin "43") (pinfunction "RD9_43") (pintype "bidirectional"))
      (node (ref "R203") (pin "1") (pinfunction "P$1_1") (pintype "bidirectional"))
    )
    (net (code "74") (name "SW1") (class "Default")
      (node (ref "IC2") (pin "44") (pinfunction "RD10_44") (pintype "bidirectional"))
      (node (ref "R205") (pin "1") (pinfunction "P$1_1") (pintype "bidirectional"))
    )
    (net (code "75") (name "VBAT") (class "Default")
      (node (ref "BAT1") (pin "3") (pinfunction "+_3") (pintype "power_in"))
      (node (ref "C5") (pin "1") (pinfunction "1_1") (pintype "passive"))
      (node (ref "IC1") (pin "19") (pinfunction "BAT_19") (pintype "bidirectional"))
      (node (ref "IC2") (pin "16") (pinfunction "RB0_16") (pintype "bidirectional"))
      (node (ref "Q1") (pin "3") (pinfunction "D_3") (pintype "passive"))
      (node (ref "R9") (pin "2") (pinfunction "2_2") (pintype "passive"))
    )
    (net (code "76") (name "VBUS") (class "Default")
      (node (ref "C1") (pin "1") (pinfunction "1_1") (pintype "passive"))
      (node (ref "IC1") (pin "21") (pinfunction "VBUS_21") (pintype "bidirectional"))
      (node (ref "R1") (pin "2") (pinfunction "2_2") (pintype "passive"))
      (node (ref "R206") (pin "2") (pinfunction "P$2_2") (pintype "bidirectional"))
      (node (ref "X1") (pin "1") (pinfunction "1_1") (pintype "input"))
    )
    (net (code "77") (name "VOUT") (class "Default")
      (node (ref "C2") (pin "1") (pinfunction "1_1") (pintype "passive"))
      (node (ref "C4") (pin "1") (pinfunction "1_1") (pintype "passive"))
      (node (ref "IC1") (pin "20") (pinfunction "VOUT_20") (pintype "bidirectional"))
      (node (ref "IC1") (pin "9") (pinfunction "VIN1_9") (pintype "bidirectional"))
      (node (ref "L11") (pin "P$2") (pinfunction "P$2_P$2") (pintype "bidirectional"))
      (node (ref "Q1") (pin "2") (pinfunction "S_2") (pintype "passive"))
    )
    (net (code "78") (name "W") (class "Default")
      (node (ref "IC2") (pin "1") (pinfunction "RE5_1") (pintype "bidirectional"))
      (node (ref "IC3") (pin "3") (pinfunction "WP#/IO2_3") (pintype "bidirectional"))
    )
    (net (code "79") (name "unconnected-(IC2-INT0{slash}RD0-Pad46)") (class "Default")
      (node (ref "IC2") (pin "46") (pinfunction "INT0/RD0_46") (pintype "bidirectional"))
    )
    (net (code "80") (name "unconnected-(IC2-RD11-Pad45)") (class "Default")
      (node (ref "IC2") (pin "45") (pinfunction "RD11_45") (pintype "bidirectional"))
    )
    (net (code "81") (name "unconnected-(IC2-RE1-Pad61)") (class "Default")
      (node (ref "IC2") (pin "61") (pinfunction "RE1_61") (pintype "bidirectional"))
    )
    (net (code "82") (name "unconnected-(IC2-RE2-Pad62)") (class "Default")
      (node (ref "IC2") (pin "62") (pinfunction "RE2_62") (pintype "bidirectional"))
    )
    (net (code "83") (name "unconnected-(IC2-RE3-Pad63)") (class "Default")
      (node (ref "IC2") (pin "63") (pinfunction "RE3_63") (pintype "bidirectional"))
    )
    (net (code "84") (name "unconnected-(IC2-RE7-Pad3)") (class "Default")
      (node (ref "IC2") (pin "3") (pinfunction "RE7_3") (pintype "bidirectional"))
    )
    (net (code "85") (name "unconnected-(JP1-Pad6)") (class "Default")
      (node (ref "JP1") (pin "6") (pinfunction "6_6") (pintype "passive"))
    )
    (net (code "86") (name "unconnected-(MOD1-NC-Pad2)") (class "Default")
      (node (ref "MOD1") (pin "2") (pinfunction "NC_2") (pintype "bidirectional"))
    )
    (net (code "87") (name "unconnected-(MOD1-NC-Pad3)") (class "Default")
      (node (ref "MOD1") (pin "3") (pinfunction "NC_3") (pintype "bidirectional"))
    )
    (net (code "88") (name "unconnected-(MOD1-NC-Pad4)") (class "Default")
      (node (ref "MOD1") (pin "4") (pinfunction "NC_4") (pintype "bidirectional"))
    )
    (net (code "89") (name "unconnected-(MOD1-NC-Pad5)") (class "Default")
      (node (ref "MOD1") (pin "5") (pinfunction "NC_5") (pintype "bidirectional"))
    )
    (net (code "90") (name "unconnected-(MOD1-NC-Pad6)") (class "Default")
      (node (ref "MOD1") (pin "6") (pinfunction "NC_6") (pintype "bidirectional"))
    )
    (net (code "91") (name "unconnected-(MOD1-NC-Pad8)") (class "Default")
      (node (ref "MOD1") (pin "8") (pinfunction "NC_8") (pintype "bidirectional"))
    )
    (net (code "92") (name "unconnected-(MOD1-NC-Pad9)") (class "Default")
      (node (ref "MOD1") (pin "9") (pinfunction "NC_9") (pintype "bidirectional"))
    )
    (net (code "93") (name "unconnected-(MOD1-NC-Pad11)") (class "Default")
      (node (ref "MOD1") (pin "11") (pinfunction "NC_11") (pintype "bidirectional"))
    )
    (net (code "94") (name "unconnected-(MOD1-NC-Pad12)") (class "Default")
      (node (ref "MOD1") (pin "12") (pinfunction "NC_12") (pintype "bidirectional"))
    )
    (net (code "95") (name "unconnected-(MOD1-NC-Pad13)") (class "Default")
      (node (ref "MOD1") (pin "13") (pinfunction "NC_13") (pintype "bidirectional"))
    )
    (net (code "96") (name "unconnected-(MOD1-NC-Pad14)") (class "Default")
      (node (ref "MOD1") (pin "14") (pinfunction "NC_14") (pintype "bidirectional"))
    )
    (net (code "97") (name "unconnected-(MOD1-NC-Pad15)") (class "Default")
      (node (ref "MOD1") (pin "15") (pinfunction "NC_15") (pintype "bidirectional"))
    )
    (net (code "98") (name "unconnected-(MOD1-NC-Pad21)") (class "Default")
      (node (ref "MOD1") (pin "21") (pinfunction "NC_21") (pintype "bidirectional"))
    )
    (net (code "99") (name "unconnected-(MOD1-NC-Pad22)") (class "Default")
      (node (ref "MOD1") (pin "22") (pinfunction "NC_22") (pintype "bidirectional"))
    )
    (net (code "100") (name "unconnected-(MOD1-NC-Pad24)") (class "Default")
      (node (ref "MOD1") (pin "24") (pinfunction "NC_24") (pintype "bidirectional"))
    )
    (net (code "101") (name "unconnected-(MOD1-NC-Pad31)") (class "Default")
      (node (ref "MOD1") (pin "31") (pinfunction "NC_31") (pintype "bidirectional"))
    )
    (net (code "102") (name "unconnected-(SW2-Pad3)") (class "Default")
      (node (ref "SW2") (pin "3") (pinfunction "3_3") (pintype "bidirectional"))
    )
  )
)
